# D143_01A01-V9821S.net
KiCad netlist of a schematic drawn in Altium Designer
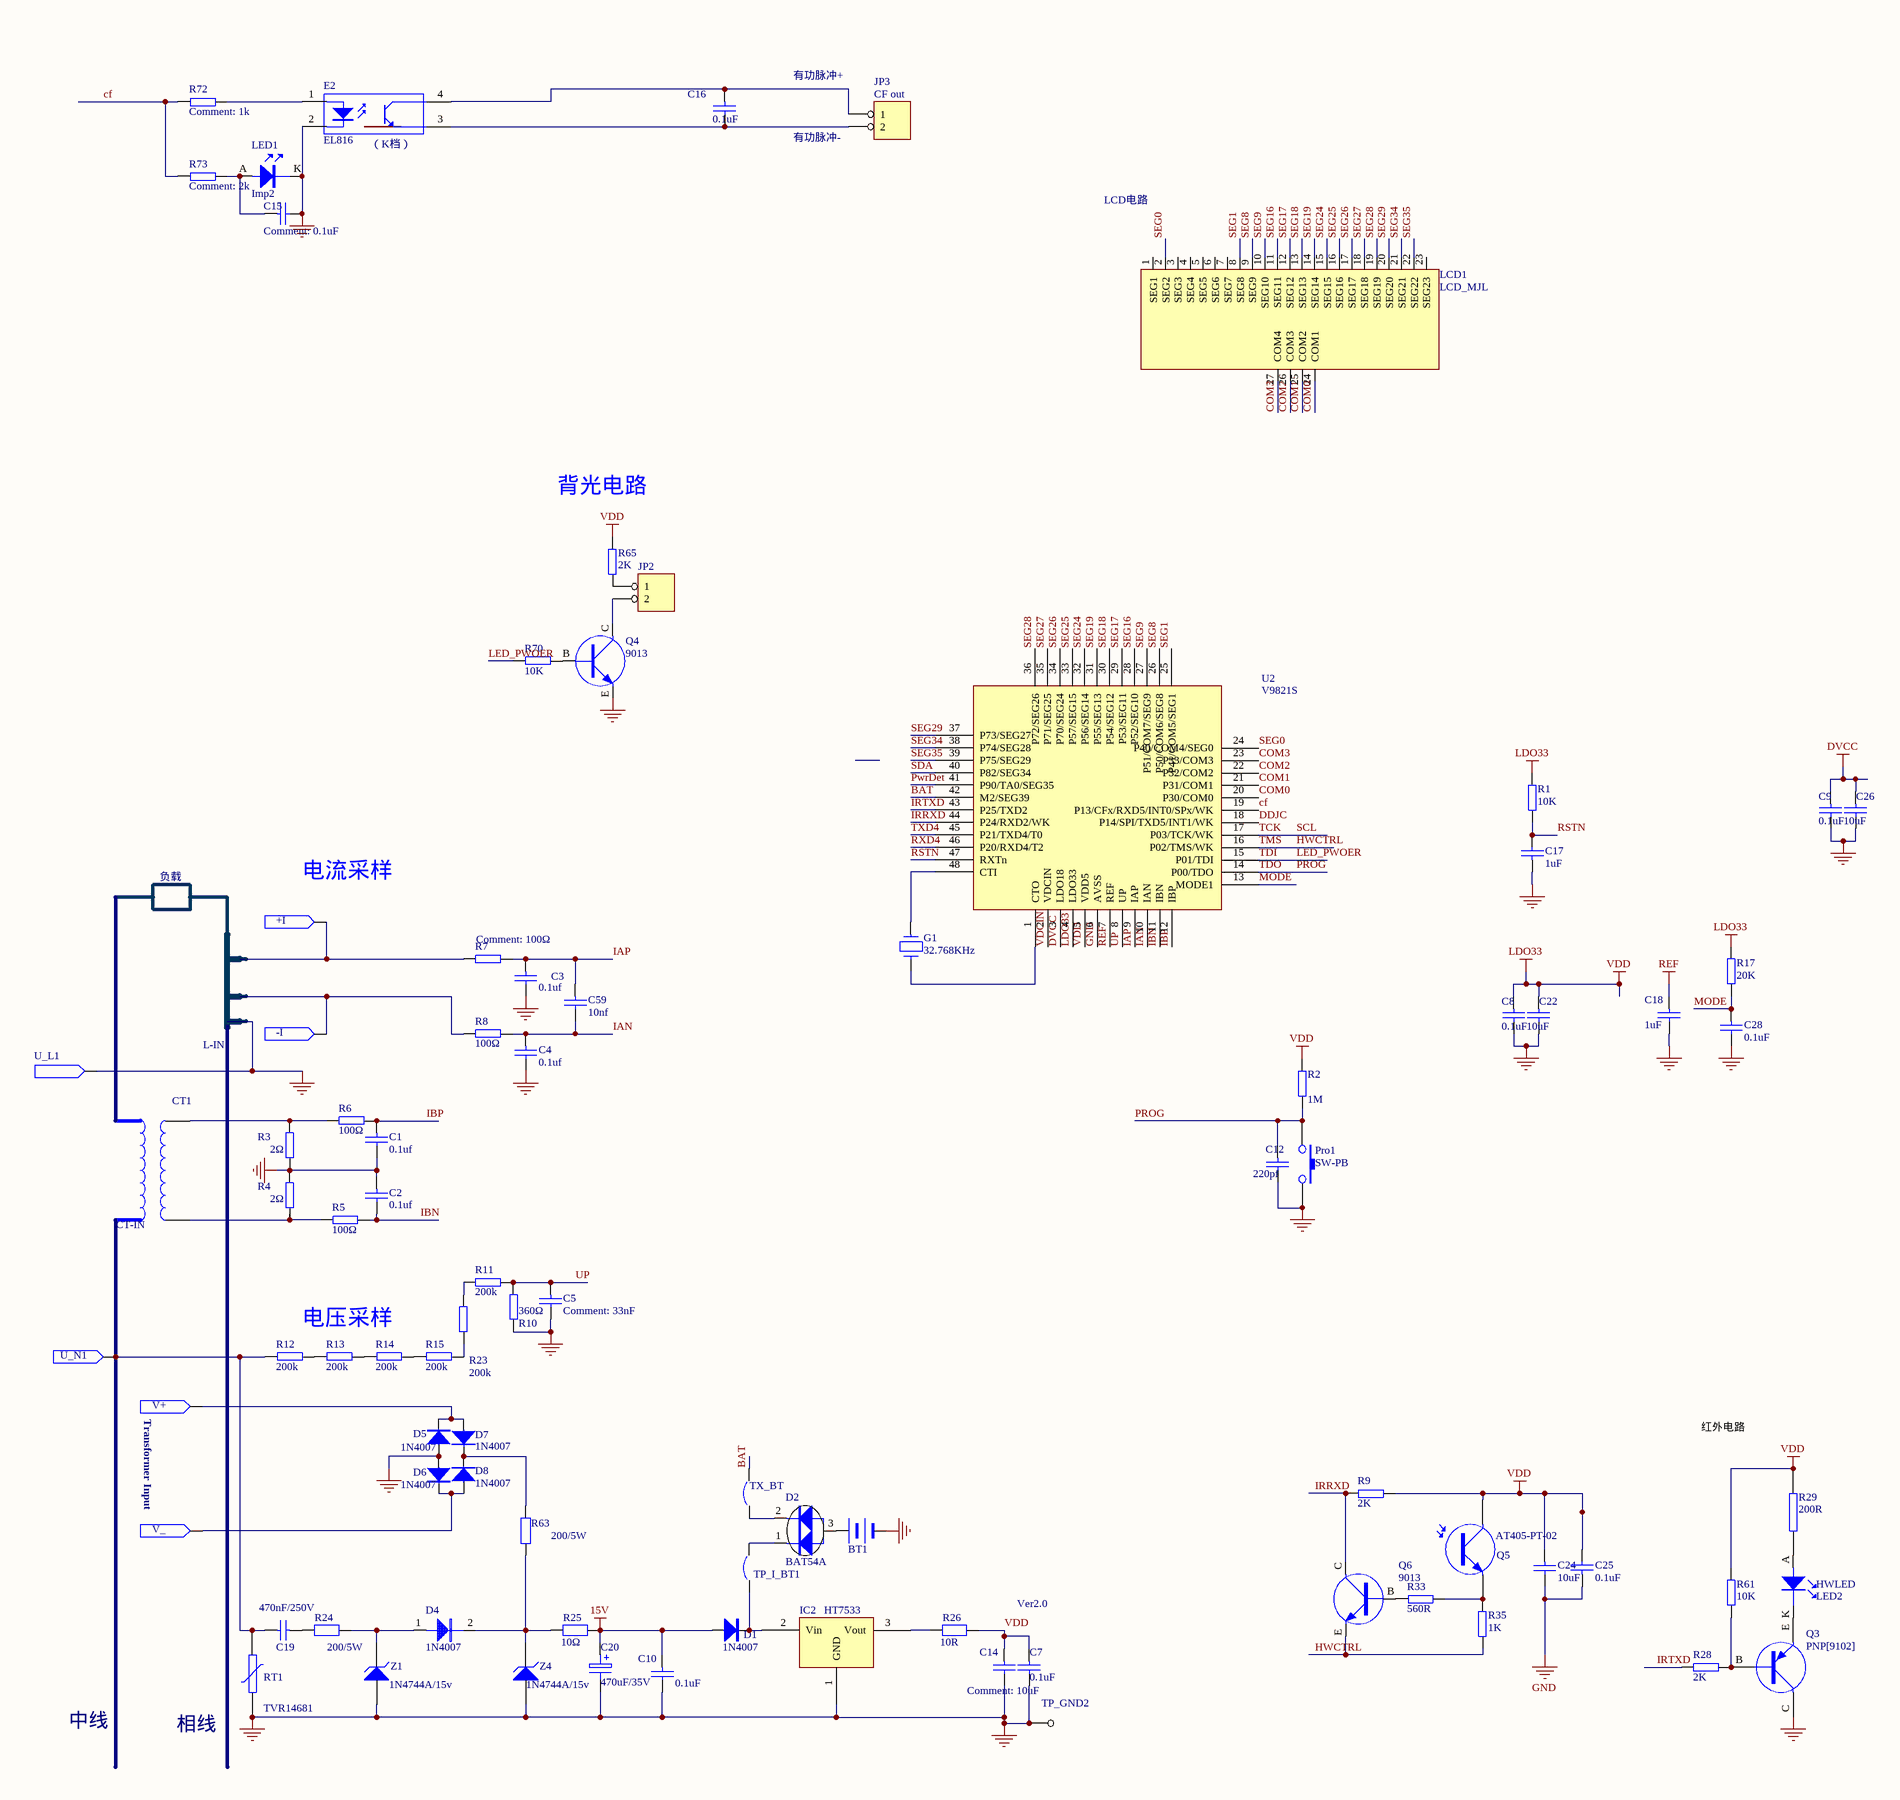
[diagram p0: D143.01A01-V9821S.SchDoc, left]
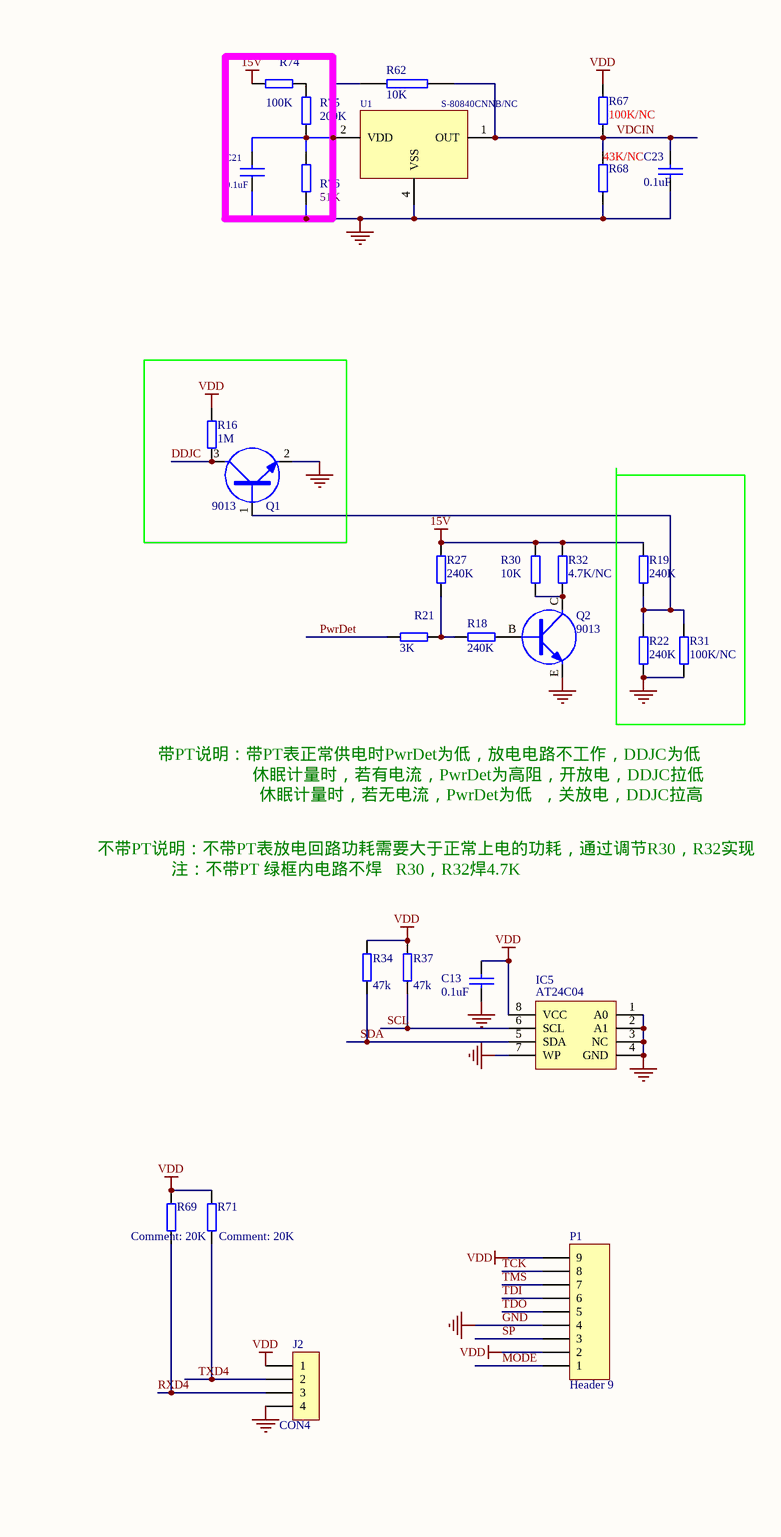
[diagram p1: D143.01A01-V9821S.SchDoc, right]

(export (version "E")
  (design (tool "Eeschema 10.0.6"))
  (components
    (comp (ref "+I") (value "~") (footprint "PAD") (libsource (lib "*") (part "Pro2C.tmp_UnNamed_44")))
    (comp (ref "-I") (value "~") (footprint "PAD") (libsource (lib "*") (part "Pro2C.tmp_UnNamed_44")))
    (comp (ref "BT1")
      (value "BT1")
      (footprint "BAT")
      (description "Battery")
      (libsource (lib "*") (part "BATTERY"))
    )
    (comp (ref "C1")
      (value "0.1uf")
      (footprint "0603C")
      (description "Capacitor")
      (libsource (lib "*") (part "CAP"))
    )
    (comp (ref "C2")
      (value "0.1uf")
      (footprint "0603C")
      (description "Capacitor")
      (libsource (lib "*") (part "CAP"))
    )
    (comp (ref "C3")
      (value "0.1uf")
      (footprint "0603C")
      (description "Capacitor")
      (libsource (lib "*") (part "CAP"))
    )
    (comp (ref "C4")
      (value "0.1uf")
      (footprint "0603C")
      (description "Capacitor")
      (libsource (lib "*") (part "CAP"))
    )
    (comp (ref "C5")
      (value "33nF")
      (footprint "0603C")
      (description "Capacitor")
      (libsource (lib "*") (part "CAP"))
    )
    (comp (ref "C7")
      (value "0.1uF")
      (footprint "0603C")
      (description "Capacitor")
      (libsource (lib "*") (part "CAP"))
    )
    (comp (ref "C8")
      (value "0.1uF")
      (footprint "0603C")
      (description "Capacitor")
      (libsource (lib "*") (part "CAP"))
    )
    (comp (ref "C9")
      (value "0.1uF")
      (footprint "0603C")
      (description "Capacitor")
      (libsource (lib "*") (part "CAP"))
    )
    (comp (ref "C10")
      (value "0.1uF")
      (footprint "0603C")
      (description "Capacitor")
      (libsource (lib "*") (part "CAP"))
    )
    (comp (ref "C12")
      (value "220pf")
      (footprint "0603C")
      (description "Capacitor")
      (libsource (lib "*") (part "CAP"))
    )
    (comp (ref "C13")
      (value "0.1uF")
      (footprint "0603C")
      (description "Capacitor")
      (libsource (lib "*") (part "CAP"))
    )
    (comp (ref "C14")
      (value "10uF")
      (footprint "0805C")
      (description "Capacitor")
      (libsource (lib "*") (part "CAP"))
    )
    (comp (ref "C15")
      (value "0.1uF")
      (footprint "0603C")
      (description "Capacitor")
      (libsource (lib "*") (part "CAP"))
    )
    (comp (ref "C16")
      (value "0.1uF")
      (footprint "0603C")
      (description "Capacitor")
      (libsource (lib "*") (part "CAP"))
    )
    (comp (ref "C17")
      (value "1uF")
      (footprint "0603C")
      (description "Capacitor")
      (libsource (lib "*") (part "CAP"))
    )
    (comp (ref "C18")
      (value "1uF")
      (footprint "0805C")
      (description "Capacitor")
      (libsource (lib "*") (part "CAP"))
    )
    (comp (ref "C19")
      (value "470nF/250V")
      (footprint "CAP0.47UF/250V")
      (description "Capacitor (Semiconductor SIM Model)")
      (fields (field (name "PUBLISHER") "*"))
      (libsource (lib "*") (part "Cap Semi"))
    )
    (comp (ref "C20")
      (value "470uF/35V")
      (footprint "RB.2/.4")
      (libsource (lib "*") (part "ProB204.TMP_UnNamed_47"))
    )
    (comp (ref "C21") (value "0.1uF") (footprint "0603C") (libsource (lib "*") (part "CAP NP")))
    (comp (ref "C22")
      (value "10uF")
      (footprint "0805C")
      (description "Capacitor")
      (libsource (lib "*") (part "CAP"))
    )
    (comp (ref "C23")
      (value "0.1uF")
      (footprint "0603C")
      (description "Capacitor")
      (libsource (lib "*") (part "CAP"))
    )
    (comp (ref "C24")
      (value "10uF")
      (footprint "0805c")
      (description "Capacitor")
      (libsource (lib "*") (part "CAP"))
    )
    (comp (ref "C25") (value "0.1uF") (footprint "0603C") (libsource (lib "*") (part "CAP")))
    (comp (ref "C26")
      (value "10uF")
      (footprint "0805C")
      (description "Capacitor")
      (libsource (lib "*") (part "CAP"))
    )
    (comp (ref "C28")
      (value "0.1uF")
      (footprint "0603C")
      (description "Capacitor")
      (libsource (lib "*") (part "CAP"))
    )
    (comp (ref "C59")
      (value "10nf")
      (footprint "0603C")
      (description "Capacitor")
      (libsource (lib "*") (part "CAP"))
    )
    (comp (ref "CT1") (value "CT-IN") (footprint "CT") (libsource (lib "*") (part "WZ-CT-S")))
    (comp (ref "D1") (value "1N4007") (footprint "MLL41") (libsource (lib "*") (part "WF_D")))
    (comp (ref "D2")
      (value "BAT54A")
      (footprint "SOT_23")
      (description "共阳")
      (libsource (lib "BASIC") (part "BAT54A"))
    )
    (comp (ref "D4")
      (value "1N4007")
      (footprint "DIODE-L")
      (libsource (lib "*") (part "ProB204.TMP_UnNamed_35"))
    )
    (comp (ref "D5") (value "1N4007") (footprint "MLL41") (libsource (lib "*") (part "WF_D")))
    (comp (ref "D6") (value "1N4007") (footprint "MLL41") (libsource (lib "*") (part "WF_D")))
    (comp (ref "D7") (value "1N4007") (footprint "MLL41") (libsource (lib "*") (part "WF_D")))
    (comp (ref "D8") (value "1N4007") (footprint "MLL41") (libsource (lib "*") (part "WF_D")))
    (comp (ref "E2") (value "EL816") (footprint "SOP-4") (libsource (lib "*") (part "TL521")))
    (comp (ref "G1")
      (value "32.768KHz")
      (footprint "OSC")
      (description "Crystal")
      (libsource (lib "*") (part "WF_X_1"))
    )
    (comp (ref "IC2") (value "HT7533") (footprint "SOT-89") (libsource (lib "*") (part "HT7150")))
    (comp (ref "IC5") (value "AT24C04") (footprint "SOP8") (libsource (lib "*") (part "AT24256")))
    (comp (ref "J2")
      (value "CON4")
      (footprint "SIP4")
      (description "Connector")
      (libsource (lib "*") (part "CON4"))
    )
    (comp (ref "JP2") (value "~") (footprint "SIP2") (libsource (lib "*") (part "HEADER 2")))
    (comp (ref "JP3") (value "CF out") (footprint "ct") (libsource (lib "*") (part "HEADER 2")))
    (comp (ref "LCD1") (value "LCD_MJL") (footprint "LCD_MJL") (libsource (lib "*") (part "LCD_MJL")))
    (comp (ref "LED1") (value "Imp2") (footprint "LED") (libsource (lib "*") (part "LED")))
    (comp (ref "LED2") (value "HWLED") (footprint "LED") (libsource (lib "*") (part "LED")))
    (comp (ref "P1")
      (value "Header 9")
      (footprint "CONNECT1")
      (description "Header, 9-Pin")
      (fields (field (name "PUBLISHER") "Altium Limited"))
      (libsource (lib "*") (part "Header 9"))
    )
    (comp (ref "Pro1") (value "SW-PB") (footprint "KEY1") (libsource (lib "*") (part "SW-PB")))
    (comp (ref "Q1") (value "9013") (footprint "SOT-23") (libsource (lib "") (part "NPN_1")))
    (comp (ref "Q2") (value "9013") (footprint "SOT-23-EBC") (libsource (lib "*") (part "NPN")))
    (comp (ref "Q3") (value "PNP[9102]") (footprint "SOT-23-EBC") (libsource (lib "*") (part "PNP[9102]")))
    (comp (ref "Q4") (value "9013") (footprint "SOT-23-EBC") (libsource (lib "*") (part "NPN")))
    (comp (ref "Q5") (value "AT405-PT-02") (footprint "LED2") (libsource (lib "*") (part "3244SC")))
    (comp (ref "Q6") (value "9013") (footprint "SOT-23-EBC") (libsource (lib "*") (part "NPN")))
    (comp (ref "R1") (value "10K") (footprint "0603R") (libsource (lib "*") (part "REST_S")))
    (comp (ref "R2") (value "1M") (footprint "0603R") (libsource (lib "*") (part "REST_S")))
    (comp (ref "R3") (value "2Ω") (footprint "0805R") (libsource (lib "*") (part "REST_S")))
    (comp (ref "R4") (value "2Ω") (footprint "0805R") (libsource (lib "*") (part "REST_S")))
    (comp (ref "R5") (value "100Ω") (footprint "0603R") (libsource (lib "*") (part "REST_S")))
    (comp (ref "R6") (value "100Ω") (footprint "0603R") (libsource (lib "*") (part "REST_S")))
    (comp (ref "R7") (value "100Ω") (footprint "0603R") (libsource (lib "*") (part "REST_S")))
    (comp (ref "R8") (value "100Ω") (footprint "0603R") (libsource (lib "*") (part "REST_S")))
    (comp (ref "R9") (value "2K") (footprint "0603R") (libsource (lib "*") (part "R")))
    (comp (ref "R10") (value "360Ω") (footprint "0805R") (libsource (lib "*") (part "REST_S")))
    (comp (ref "R11") (value "200k") (footprint "0805R") (libsource (lib "*") (part "REST_S")))
    (comp (ref "R12") (value "200k") (footprint "0805R") (libsource (lib "*") (part "REST_S")))
    (comp (ref "R13") (value "200k") (footprint "0805R") (libsource (lib "*") (part "REST_S")))
    (comp (ref "R14") (value "200k") (footprint "0805R") (libsource (lib "*") (part "REST_S")))
    (comp (ref "R15") (value "200k") (footprint "0805R") (libsource (lib "*") (part "REST_S")))
    (comp (ref "R16") (value "1M") (footprint "0603R") (libsource (lib "*") (part "REST_S")))
    (comp (ref "R17") (value "20K") (footprint "0603R") (libsource (lib "*") (part "REST_S")))
    (comp (ref "R18") (value "240K") (footprint "0603R") (libsource (lib "*") (part "REST_S")))
    (comp (ref "R19") (value "240K") (footprint "0603R") (libsource (lib "*") (part "REST_S")))
    (comp (ref "R21") (value "3K") (footprint "0603R") (libsource (lib "*") (part "REST_S")))
    (comp (ref "R22") (value "240K") (footprint "0603R") (libsource (lib "*") (part "REST_S")))
    (comp (ref "R23") (value "200k") (footprint "0805R") (libsource (lib "*") (part "REST_S")))
    (comp (ref "R24")
      (value "200/5W")
      (footprint "AXIAL0.8A")
      (description "Resistor")
      (fields (field (name "PUBLISHER") "*"))
      (libsource (lib "*") (part "Res2"))
    )
    (comp (ref "R25")
      (value "10Ω")
      (footprint "0805R")
      (description "Resistor")
      (fields (field (name "PUBLISHER") "*"))
      (libsource (lib "*") (part "Res2"))
    )
    (comp (ref "R26")
      (value "10R")
      (footprint "0805R")
      (description "Resistor")
      (fields (field (name "PUBLISHER") "*"))
      (libsource (lib "*") (part "Res2"))
    )
    (comp (ref "R27") (value "240K") (footprint "0603R") (libsource (lib "*") (part "REST_S")))
    (comp (ref "R28") (value "2K") (footprint "0603R") (libsource (lib "*") (part "R")))
    (comp (ref "R29") (value "200R") (footprint "0603R") (libsource (lib "*") (part "RES2")))
    (comp (ref "R30") (value "10K") (footprint "0603R") (libsource (lib "*") (part "REST_S")))
    (comp (ref "R31") (value "100K/NC") (footprint "0603R") (libsource (lib "*") (part "REST_S")))
    (comp (ref "R32") (value "4.7K/NC") (footprint "0603R") (libsource (lib "*") (part "REST_S")))
    (comp (ref "R33") (value "560R") (footprint "0603R") (libsource (lib "*") (part "R")))
    (comp (ref "R34") (value "47k") (footprint "0603R") (libsource (lib "*") (part "REST_S")))
    (comp (ref "R35") (value "1K") (footprint "0603R") (libsource (lib "*") (part "R")))
    (comp (ref "R37") (value "47k") (footprint "0603R") (libsource (lib "*") (part "REST_S")))
    (comp (ref "R61") (value "10K") (footprint "0603R") (libsource (lib "*") (part "R")))
    (comp (ref "R62") (value "10K") (footprint "0603R") (libsource (lib "*") (part "RES2")))
    (comp (ref "R63")
      (value "200/5W")
      (footprint "AXIAL0.8A")
      (description "Resistor")
      (fields (field (name "PUBLISHER") "*"))
      (libsource (lib "") (part "Res2_1"))
    )
    (comp (ref "R65") (value "2K") (footprint "0603R") (libsource (lib "*") (part "R")))
    (comp (ref "R67") (value "100K/NC") (footprint "0603R") (libsource (lib "*") (part "REST_S")))
    (comp (ref "R68") (value "43K/NC") (footprint "0603R") (libsource (lib "*") (part "REST_S")))
    (comp (ref "R69") (value "20K") (footprint "0603R") (libsource (lib "*") (part "REST_S")))
    (comp (ref "R70") (value "10K") (footprint "0603R") (libsource (lib "*") (part "R")))
    (comp (ref "R71") (value "20K") (footprint "0603R") (libsource (lib "*") (part "REST_S")))
    (comp (ref "R72") (value "1k") (footprint "0603R") (libsource (lib "*") (part "REST_S")))
    (comp (ref "R73") (value "2k") (footprint "0603R") (libsource (lib "*") (part "REST_S")))
    (comp (ref "R74") (value "100K") (footprint "0805R") (libsource (lib "*") (part "REST_S")))
    (comp (ref "R75") (value "200K") (footprint "0805R") (libsource (lib "*") (part "REST_S")))
    (comp (ref "R76") (value "51K") (footprint "0805R") (libsource (lib "*") (part "REST_S")))
    (comp (ref "RT1") (value "TVR14681") (footprint "YM20K681") (libsource (lib "*") (part "WF_RESV")))
    (comp (ref "TP_GND2")
      (value "TP")
      (footprint "TEST0")
      (description "TEST POINT")
      (libsource (lib "*") (part "TP_T"))
    )
    (comp (ref "TP_I_BT1")
      (value "CIRCUIT BREAKER")
      (footprint "JUMP")
      (description "Circuit Breaker")
      (libsource (lib "*") (part "CIRCUIT BREAKER"))
    )
    (comp (ref "TX_BT")
      (value "CIRCUIT BREAKER")
      (footprint "JUMP")
      (description "Circuit Breaker")
      (libsource (lib "*") (part "CIRCUIT BREAKER"))
    )
    (comp (ref "U1")
      (value "S-80840CNNB/NC")
      (footprint "SC-82AB")
      (description "电源检测IC")
      (libsource (lib "*") (part "S808XX_CLNB"))
    )
    (comp (ref "U2") (value "V9821S") (libsource (lib "Schlib1") (part "Component_1")))
    (comp (ref "U_L1") (value "~") (footprint "PAD") (libsource (lib "*") (part "Pro2C.tmp_UnNamed_44")))
    (comp (ref "U_N1") (value "~") (footprint "PAD") (libsource (lib "*") (part "Pro2C.tmp_UnNamed_44")))
    (comp (ref "V+") (value "~") (footprint "PAD") (libsource (lib "*") (part "Pro2C.tmp_UnNamed_44")))
    (comp (ref "V_") (value "~") (footprint "PAD") (libsource (lib "*") (part "Pro2C.tmp_UnNamed_44")))
    (comp (ref "Z1")
      (value "1N4744A/15v")
      (footprint "DIODE")
      (description "One Watt Zener")
      (libsource (lib "*") (part "1N4734A"))
    )
    (comp (ref "Z4")
      (value "1N4744A/15v")
      (footprint "DIODE")
      (description "One Watt Zener")
      (libsource (lib "*") (part "1N4734A"))
    )
  )
  (nets
    (net (code "1") (name "/BAT") (class "Default")
      (node (ref "TX_BT") (pin "2") (pinfunction "2_2") (pintype "passive"))
      (node (ref "U2") (pin "42") (pinfunction "M2/SEG39_42") (pintype "passive"))
    )
    (net (code "2") (name "/COM0") (class "Default")
      (node (ref "LCD1") (pin "24") (pinfunction "COM1_24") (pintype "passive"))
      (node (ref "U2") (pin "20") (pinfunction "P30/COM0_20") (pintype "passive"))
    )
    (net (code "3") (name "/COM1") (class "Default")
      (node (ref "LCD1") (pin "25") (pinfunction "COM2_25") (pintype "passive"))
      (node (ref "U2") (pin "21") (pinfunction "P31/COM1_21") (pintype "passive"))
    )
    (net (code "4") (name "/COM2") (class "Default")
      (node (ref "LCD1") (pin "26") (pinfunction "COM3_26") (pintype "passive"))
      (node (ref "U2") (pin "22") (pinfunction "P32/COM2_22") (pintype "passive"))
    )
    (net (code "5") (name "/COM3") (class "Default")
      (node (ref "LCD1") (pin "27") (pinfunction "COM4_27") (pintype "passive"))
      (node (ref "U2") (pin "23") (pinfunction "P33/COM3_23") (pintype "passive"))
    )
    (net (code "6") (name "/DDJC") (class "Default")
      (node (ref "Q1") (pin "3") (pinfunction "C_3") (pintype "passive"))
      (node (ref "R16") (pin "1") (pinfunction "1_1") (pintype "passive"))
      (node (ref "U2") (pin "18") (pinfunction "P14/SPI/TXD5/INT1/WK_18") (pintype "passive"))
    )
    (net (code "7") (name "/HWCTRL") (class "Default")
      (node (ref "P1") (pin "7") (pinfunction "7_7") (pintype "passive"))
      (node (ref "Q6") (pin "E") (pinfunction "E_E") (pintype "passive"))
      (node (ref "R35") (pin "1") (pintype "passive"))
      (node (ref "U2") (pin "16") (pinfunction "P02/TMS/WK_16") (pintype "passive"))
    )
    (net (code "8") (name "/IAN") (class "Default")
      (node (ref "C4") (pin "1") (pinfunction "1_1") (pintype "passive"))
      (node (ref "C59") (pin "2") (pinfunction "2_2") (pintype "passive"))
      (node (ref "R8") (pin "1") (pinfunction "1_1") (pintype "passive"))
      (node (ref "U2") (pin "10") (pinfunction "IAN_10") (pintype "passive"))
    )
    (net (code "9") (name "/IAP") (class "Default")
      (node (ref "C3") (pin "1") (pinfunction "1_1") (pintype "passive"))
      (node (ref "C59") (pin "1") (pinfunction "1_1") (pintype "passive"))
      (node (ref "R7") (pin "1") (pinfunction "1_1") (pintype "passive"))
      (node (ref "U2") (pin "9") (pinfunction "IAP_9") (pintype "passive"))
    )
    (net (code "10") (name "/IBN") (class "Default")
      (node (ref "C2") (pin "2") (pinfunction "2_2") (pintype "passive"))
      (node (ref "R5") (pin "1") (pinfunction "1_1") (pintype "passive"))
      (node (ref "U2") (pin "11") (pinfunction "IBN_11") (pintype "passive"))
    )
    (net (code "11") (name "/IBP") (class "Default")
      (node (ref "C1") (pin "1") (pinfunction "1_1") (pintype "passive"))
      (node (ref "R6") (pin "1") (pinfunction "1_1") (pintype "passive"))
      (node (ref "U2") (pin "12") (pinfunction "IBP_12") (pintype "passive"))
    )
    (net (code "12") (name "/IRRXD") (class "Default")
      (node (ref "Q6") (pin "C") (pinfunction "C_C") (pintype "passive"))
      (node (ref "R9") (pin "1") (pintype "passive"))
      (node (ref "U2") (pin "44") (pinfunction "P24/RXD2/WK_44") (pintype "passive"))
    )
    (net (code "13") (name "/IRTXD") (class "Default")
      (node (ref "R28") (pin "2") (pintype "passive"))
      (node (ref "U2") (pin "43") (pinfunction "P25/TXD2_43") (pintype "passive"))
    )
    (net (code "14") (name "/LED_PWOER") (class "Default")
      (node (ref "P1") (pin "6") (pinfunction "6_6") (pintype "passive"))
      (node (ref "R70") (pin "2") (pintype "passive"))
      (node (ref "U2") (pin "15") (pinfunction "P01/TDI_15") (pintype "passive"))
    )
    (net (code "15") (name "/MODE") (class "Default")
      (node (ref "C28") (pin "1") (pinfunction "1_1") (pintype "passive"))
      (node (ref "P1") (pin "1") (pinfunction "1_1") (pintype "passive"))
      (node (ref "R17") (pin "2") (pinfunction "2_2") (pintype "passive"))
      (node (ref "U2") (pin "13") (pinfunction "MODE1_13") (pintype "passive"))
    )
    (net (code "16") (name "/PROG") (class "Default")
      (node (ref "C12") (pin "1") (pinfunction "1_1") (pintype "passive"))
      (node (ref "P1") (pin "5") (pinfunction "5_5") (pintype "passive"))
      (node (ref "Pro1") (pin "1") (pinfunction "1_1") (pintype "passive"))
      (node (ref "Pro1") (pin "3") (pinfunction "3_3") (pintype "passive"))
      (node (ref "R2") (pin "1") (pinfunction "1_1") (pintype "passive"))
      (node (ref "U2") (pin "14") (pinfunction "P00/TDO_14") (pintype "passive"))
    )
    (net (code "17") (name "/PwrDet") (class "Default")
      (node (ref "R21") (pin "1") (pinfunction "1_1") (pintype "passive"))
      (node (ref "U2") (pin "41") (pinfunction "P90/TA0/SEG35_41") (pintype "passive"))
    )
    (net (code "18") (name "/RSTN") (class "Default")
      (node (ref "C17") (pin "2") (pinfunction "2_2") (pintype "passive"))
      (node (ref "R1") (pin "1") (pinfunction "1_1") (pintype "passive"))
      (node (ref "U2") (pin "47") (pinfunction "RXTn_47") (pintype "passive"))
    )
    (net (code "19") (name "/RXD4") (class "Default")
      (node (ref "J2") (pin "3") (pinfunction "3_3") (pintype "passive"))
      (node (ref "R69") (pin "2") (pinfunction "2_2") (pintype "passive"))
      (node (ref "U2") (pin "46") (pinfunction "P20/RXD4/T2_46") (pintype "passive"))
    )
    (net (code "20") (name "/SCL") (class "Default")
      (node (ref "IC5") (pin "6") (pinfunction "SCL_6") (pintype "passive"))
      (node (ref "P1") (pin "8") (pinfunction "8_8") (pintype "passive"))
      (node (ref "R37") (pin "1") (pinfunction "1_1") (pintype "passive"))
      (node (ref "U2") (pin "17") (pinfunction "P03/TCK/WK_17") (pintype "passive"))
    )
    (net (code "21") (name "/SDA") (class "Default")
      (node (ref "IC5") (pin "5") (pinfunction "SDA_5") (pintype "passive"))
      (node (ref "R34") (pin "1") (pinfunction "1_1") (pintype "passive"))
      (node (ref "U2") (pin "40") (pinfunction "P82/SEG34_40") (pintype "passive"))
    )
    (net (code "22") (name "/SEG0") (class "Default")
      (node (ref "LCD1") (pin "2") (pinfunction "SEG2_2") (pintype "passive"))
      (node (ref "U2") (pin "24") (pinfunction "P40/COM4/SEG0_24") (pintype "passive"))
    )
    (net (code "23") (name "/SEG1") (class "Default")
      (node (ref "LCD1") (pin "8") (pinfunction "SEG8_8") (pintype "passive"))
      (node (ref "U2") (pin "25") (pinfunction "P41/COM5/SEG1_25") (pintype "passive"))
    )
    (net (code "24") (name "/SEG8") (class "Default")
      (node (ref "LCD1") (pin "9") (pinfunction "SEG9_9") (pintype "passive"))
      (node (ref "U2") (pin "26") (pinfunction "P50/COM6/SEG8_26") (pintype "passive"))
    )
    (net (code "25") (name "/SEG9") (class "Default")
      (node (ref "LCD1") (pin "10") (pinfunction "SEG10_10") (pintype "passive"))
      (node (ref "U2") (pin "27") (pinfunction "P51/COM7/SEG9_27") (pintype "passive"))
    )
    (net (code "26") (name "/SEG16") (class "Default")
      (node (ref "LCD1") (pin "11") (pinfunction "SEG11_11") (pintype "passive"))
      (node (ref "U2") (pin "28") (pinfunction "P52/SEG10_28") (pintype "passive"))
    )
    (net (code "27") (name "/SEG17") (class "Default")
      (node (ref "LCD1") (pin "12") (pinfunction "SEG12_12") (pintype "passive"))
      (node (ref "U2") (pin "29") (pinfunction "P53/SEG11_29") (pintype "passive"))
    )
    (net (code "28") (name "/SEG18") (class "Default")
      (node (ref "LCD1") (pin "13") (pinfunction "SEG13_13") (pintype "passive"))
      (node (ref "U2") (pin "30") (pinfunction "P54/SEG12_30") (pintype "passive"))
    )
    (net (code "29") (name "/SEG19") (class "Default")
      (node (ref "LCD1") (pin "14") (pinfunction "SEG14_14") (pintype "passive"))
      (node (ref "U2") (pin "31") (pinfunction "P55/SEG13_31") (pintype "passive"))
    )
    (net (code "30") (name "/SEG24") (class "Default")
      (node (ref "LCD1") (pin "15") (pinfunction "SEG15_15") (pintype "passive"))
      (node (ref "U2") (pin "32") (pinfunction "P56/SEG14_32") (pintype "passive"))
    )
    (net (code "31") (name "/SEG25") (class "Default")
      (node (ref "LCD1") (pin "16") (pinfunction "SEG16_16") (pintype "passive"))
      (node (ref "U2") (pin "33") (pinfunction "P57/SEG15_33") (pintype "passive"))
    )
    (net (code "32") (name "/SEG26") (class "Default")
      (node (ref "LCD1") (pin "17") (pinfunction "SEG17_17") (pintype "passive"))
      (node (ref "U2") (pin "34") (pinfunction "P70/SEG24_34") (pintype "passive"))
    )
    (net (code "33") (name "/SEG27") (class "Default")
      (node (ref "LCD1") (pin "18") (pinfunction "SEG18_18") (pintype "passive"))
      (node (ref "U2") (pin "35") (pinfunction "P71/SEG25_35") (pintype "passive"))
    )
    (net (code "34") (name "/SEG28") (class "Default")
      (node (ref "LCD1") (pin "19") (pinfunction "SEG19_19") (pintype "passive"))
      (node (ref "U2") (pin "36") (pinfunction "P72/SEG26_36") (pintype "passive"))
    )
    (net (code "35") (name "/SEG29") (class "Default")
      (node (ref "LCD1") (pin "20") (pinfunction "SEG20_20") (pintype "passive"))
      (node (ref "U2") (pin "37") (pinfunction "P73/SEG27_37") (pintype "passive"))
    )
    (net (code "36") (name "/SEG34") (class "Default")
      (node (ref "LCD1") (pin "21") (pinfunction "SEG21_21") (pintype "passive"))
      (node (ref "U2") (pin "38") (pinfunction "P74/SEG28_38") (pintype "passive"))
    )
    (net (code "37") (name "/SEG35") (class "Default")
      (node (ref "LCD1") (pin "22") (pinfunction "SEG22_22") (pintype "passive"))
      (node (ref "U2") (pin "39") (pinfunction "P75/SEG29_39") (pintype "passive"))
    )
    (net (code "38") (name "/SP") (class "Default")
      (node (ref "P1") (pin "3") (pinfunction "3_3") (pintype "passive"))
    )
    (net (code "39") (name "/TXD4") (class "Default")
      (node (ref "J2") (pin "2") (pinfunction "2_2") (pintype "passive"))
      (node (ref "R71") (pin "2") (pinfunction "2_2") (pintype "passive"))
      (node (ref "U2") (pin "45") (pinfunction "P21/TXD4/T0_45") (pintype "passive"))
    )
    (net (code "40") (name "/UP") (class "Default")
      (node (ref "C5") (pin "1") (pinfunction "1_1") (pintype "passive"))
      (node (ref "R10") (pin "1") (pinfunction "1_1") (pintype "passive"))
      (node (ref "R11") (pin "2") (pinfunction "2_2") (pintype "passive"))
      (node (ref "U2") (pin "8") (pinfunction "UP_8") (pintype "passive"))
    )
    (net (code "41") (name "/VDCIN") (class "Default")
      (node (ref "C23") (pin "1") (pinfunction "1_1") (pintype "passive"))
      (node (ref "R62") (pin "1") (pinfunction "1_1") (pintype "passive"))
      (node (ref "R67") (pin "1") (pinfunction "1_1") (pintype "passive"))
      (node (ref "R68") (pin "2") (pinfunction "2_2") (pintype "passive"))
      (node (ref "U1") (pin "1") (pinfunction "OUT_1") (pintype "passive"))
      (node (ref "U2") (pin "2") (pinfunction "VDCIN_2") (pintype "passive"))
    )
    (net (code "42") (name "/cf") (class "Default")
      (node (ref "R72") (pin "1") (pinfunction "1_1") (pintype "passive"))
      (node (ref "R73") (pin "1") (pinfunction "1_1") (pintype "passive"))
      (node (ref "U2") (pin "19") (pinfunction "P13/CFx/RXD5/INT0/SPx/WK_19") (pintype "passive"))
    )
    (net (code "43") (name "15V") (class "Default")
      (node (ref "C10") (pin "1") (pinfunction "1_1") (pintype "passive"))
      (node (ref "C20") (pin "1") (pintype "passive"))
      (node (ref "D1") (pin "1") (pinfunction "A_1") (pintype "passive"))
      (node (ref "R19") (pin "1") (pinfunction "1_1") (pintype "passive"))
      (node (ref "R25") (pin "1") (pinfunction "1_1") (pintype "passive"))
      (node (ref "R27") (pin "1") (pinfunction "1_1") (pintype "passive"))
      (node (ref "R30") (pin "2") (pinfunction "2_2") (pintype "passive"))
      (node (ref "R32") (pin "2") (pinfunction "2_2") (pintype "passive"))
      (node (ref "R74") (pin "2") (pinfunction "2_2") (pintype "passive"))
    )
    (net (code "44") (name "DVCC") (class "Default")
      (node (ref "C26") (pin "1") (pinfunction "1_1") (pintype "passive"))
      (node (ref "C9") (pin "1") (pinfunction "1_1") (pintype "passive"))
      (node (ref "U2") (pin "3") (pinfunction "LDO18_3") (pintype "passive"))
    )
    (net (code "45") (name "GND") (class "Default")
      (node (ref "BT1") (pin "2") (pinfunction "-_2") (pintype "passive"))
      (node (ref "C1") (pin "2") (pinfunction "2_2") (pintype "passive"))
      (node (ref "C10") (pin "2") (pinfunction "2_2") (pintype "passive"))
      (node (ref "C12") (pin "2") (pinfunction "2_2") (pintype "passive"))
      (node (ref "C13") (pin "2") (pinfunction "2_2") (pintype "passive"))
      (node (ref "C14") (pin "2") (pinfunction "2_2") (pintype "passive"))
      (node (ref "C15") (pin "2") (pinfunction "2_2") (pintype "passive"))
      (node (ref "C17") (pin "1") (pinfunction "1_1") (pintype "passive"))
      (node (ref "C18") (pin "2") (pinfunction "2_2") (pintype "passive"))
      (node (ref "C2") (pin "1") (pinfunction "1_1") (pintype "passive"))
      (node (ref "C20") (pin "2") (pintype "passive"))
      (node (ref "C21") (pin "1") (pinfunction "1_1") (pintype "passive"))
      (node (ref "C22") (pin "2") (pinfunction "2_2") (pintype "passive"))
      (node (ref "C23") (pin "2") (pinfunction "2_2") (pintype "passive"))
      (node (ref "C24") (pin "2") (pinfunction "2_2") (pintype "passive"))
      (node (ref "C25") (pin "1") (pinfunction "1_1") (pintype "passive"))
      (node (ref "C26") (pin "2") (pinfunction "2_2") (pintype "passive"))
      (node (ref "C28") (pin "2") (pinfunction "2_2") (pintype "passive"))
      (node (ref "C3") (pin "2") (pinfunction "2_2") (pintype "passive"))
      (node (ref "C4") (pin "2") (pinfunction "2_2") (pintype "passive"))
      (node (ref "C5") (pin "2") (pinfunction "2_2") (pintype "passive"))
      (node (ref "C7") (pin "2") (pinfunction "2_2") (pintype "passive"))
      (node (ref "C8") (pin "2") (pinfunction "2_2") (pintype "passive"))
      (node (ref "C9") (pin "2") (pinfunction "2_2") (pintype "passive"))
      (node (ref "D5") (pin "1") (pinfunction "A_1") (pintype "passive"))
      (node (ref "D6") (pin "1") (pinfunction "A_1") (pintype "passive"))
      (node (ref "E2") (pin "2") (pinfunction "2_2") (pintype "passive"))
      (node (ref "IC2") (pin "1") (pinfunction "GND_1") (pintype "passive"))
      (node (ref "IC5") (pin "1") (pinfunction "A0_1") (pintype "passive"))
      (node (ref "IC5") (pin "2") (pinfunction "A1_2") (pintype "passive"))
      (node (ref "IC5") (pin "3") (pinfunction "NC_3") (pintype "passive"))
      (node (ref "IC5") (pin "4") (pinfunction "GND_4") (pintype "passive"))
      (node (ref "IC5") (pin "7") (pinfunction "WP_7") (pintype "passive"))
      (node (ref "J2") (pin "4") (pinfunction "4_4") (pintype "passive"))
      (node (ref "LED1") (pin "K") (pinfunction "2_K") (pintype "passive"))
      (node (ref "P1") (pin "4") (pinfunction "4_4") (pintype "passive"))
      (node (ref "Pro1") (pin "2") (pinfunction "2_2") (pintype "passive"))
      (node (ref "Pro1") (pin "4") (pinfunction "4_4") (pintype "passive"))
      (node (ref "Q1") (pin "2") (pinfunction "E_2") (pintype "passive"))
      (node (ref "Q2") (pin "E") (pinfunction "E_E") (pintype "passive"))
      (node (ref "Q3") (pin "C") (pinfunction "C_C") (pintype "passive"))
      (node (ref "Q4") (pin "E") (pinfunction "E_E") (pintype "passive"))
      (node (ref "R10") (pin "2") (pinfunction "2_2") (pintype "passive"))
      (node (ref "R22") (pin "2") (pinfunction "2_2") (pintype "passive"))
      (node (ref "R3") (pin "2") (pinfunction "2_2") (pintype "passive"))
      (node (ref "R31") (pin "1") (pinfunction "1_1") (pintype "passive"))
      (node (ref "R4") (pin "1") (pinfunction "1_1") (pintype "passive"))
      (node (ref "R68") (pin "1") (pinfunction "1_1") (pintype "passive"))
      (node (ref "R76") (pin "1") (pinfunction "1_1") (pintype "passive"))
      (node (ref "RT1") (pin "2") (pinfunction "2_2") (pintype "passive"))
      (node (ref "TP_GND2") (pin "0") (pinfunction "0_0") (pintype "passive"))
      (node (ref "U1") (pin "4") (pinfunction "VSS_4") (pintype "passive"))
      (node (ref "U2") (pin "6") (pinfunction "AVSS_6") (pintype "passive"))
      (node (ref "U_L1") (pin "1") (pintype "passive"))
      (node (ref "Z1") (pin "1") (pinfunction "A_1") (pintype "passive"))
      (node (ref "Z4") (pin "1") (pinfunction "A_1") (pintype "passive"))
    )
    (net (code "46") (name "LDO33") (class "Default")
      (node (ref "C13") (pin "1") (pinfunction "1_1") (pintype "passive"))
      (node (ref "C14") (pin "1") (pinfunction "1_1") (pintype "passive"))
      (node (ref "C22") (pin "1") (pinfunction "1_1") (pintype "passive"))
      (node (ref "C24") (pin "1") (pinfunction "1_1") (pintype "passive"))
      (node (ref "C25") (pin "2") (pinfunction "2_2") (pintype "passive"))
      (node (ref "C7") (pin "1") (pinfunction "1_1") (pintype "passive"))
      (node (ref "C8") (pin "1") (pinfunction "1_1") (pintype "passive"))
      (node (ref "IC5") (pin "8") (pinfunction "VCC_8") (pintype "passive"))
      (node (ref "J2") (pin "1") (pinfunction "1_1") (pintype "passive"))
      (node (ref "P1") (pin "2") (pinfunction "2_2") (pintype "passive"))
      (node (ref "P1") (pin "9") (pinfunction "9_9") (pintype "passive"))
      (node (ref "Q5") (pin "A") (pinfunction "C_A") (pintype "passive"))
      (node (ref "R1") (pin "2") (pinfunction "2_2") (pintype "passive"))
      (node (ref "R16") (pin "2") (pinfunction "2_2") (pintype "passive"))
      (node (ref "R17") (pin "1") (pinfunction "1_1") (pintype "passive"))
      (node (ref "R2") (pin "2") (pinfunction "2_2") (pintype "passive"))
      (node (ref "R26") (pin "1") (pinfunction "1_1") (pintype "passive"))
      (node (ref "R29") (pin "2") (pinfunction "2_2") (pintype "passive"))
      (node (ref "R34") (pin "2") (pinfunction "2_2") (pintype "passive"))
      (node (ref "R37") (pin "2") (pinfunction "2_2") (pintype "passive"))
      (node (ref "R61") (pin "1") (pintype "passive"))
      (node (ref "R65") (pin "2") (pintype "passive"))
      (node (ref "R67") (pin "2") (pinfunction "2_2") (pintype "passive"))
      (node (ref "R69") (pin "1") (pinfunction "1_1") (pintype "passive"))
      (node (ref "R71") (pin "1") (pinfunction "1_1") (pintype "passive"))
      (node (ref "R9") (pin "2") (pintype "passive"))
      (node (ref "U2") (pin "4") (pinfunction "LDO33_4") (pintype "passive"))
      (node (ref "U2") (pin "5") (pinfunction "VDD5_5") (pintype "passive"))
    )
    (net (code "47") (name "NC") (class "Default")
      (node (ref "U1") (pin "3") (pinfunction "NC_3") (pintype "passive"))
    )
    (net (code "48") (name "Net-(+I-Pad1)") (class "Default")
      (node (ref "+I") (pin "1") (pintype "passive"))
      (node (ref "R7") (pin "2") (pinfunction "2_2") (pintype "passive"))
    )
    (net (code "49") (name "Net-(-I-Pad1)") (class "Default")
      (node (ref "-I") (pin "1") (pintype "passive"))
      (node (ref "R8") (pin "2") (pinfunction "2_2") (pintype "passive"))
    )
    (net (code "50") (name "Net-(BT1-+)") (class "Default")
      (node (ref "BT1") (pin "1") (pinfunction "+_1") (pintype "passive"))
      (node (ref "D2") (pin "3") (pinfunction "3_3") (pintype "passive"))
    )
    (net (code "51") (name "Net-(C16-Pad1)") (class "Default")
      (node (ref "C16") (pin "1") (pinfunction "1_1") (pintype "passive"))
      (node (ref "E2") (pin "4") (pinfunction "4_4") (pintype "passive"))
      (node (ref "JP3") (pin "1") (pinfunction "1_1") (pintype "passive"))
    )
    (net (code "52") (name "Net-(C16-Pad2)") (class "Default")
      (node (ref "C16") (pin "2") (pinfunction "2_2") (pintype "passive"))
      (node (ref "E2") (pin "3") (pinfunction "3_3") (pintype "passive"))
      (node (ref "JP3") (pin "2") (pinfunction "2_2") (pintype "passive"))
    )
    (net (code "53") (name "Net-(C19-Pad1)") (class "Default")
      (node (ref "C19") (pin "1") (pinfunction "1_1") (pintype "passive"))
      (node (ref "R24") (pin "2") (pinfunction "2_2") (pintype "passive"))
    )
    (net (code "54") (name "Net-(C19-Pad2)") (class "Default")
      (node (ref "C19") (pin "2") (pinfunction "2_2") (pintype "passive"))
      (node (ref "R12") (pin "2") (pinfunction "2_2") (pintype "passive"))
      (node (ref "RT1") (pin "1") (pinfunction "1_1") (pintype "passive"))
      (node (ref "U_N1") (pin "1") (pintype "passive"))
    )
    (net (code "55") (name "Net-(CT1-Pad1)") (class "Default")
      (node (ref "CT1") (pin "1") (pinfunction "1_1") (pintype "passive"))
      (node (ref "R4") (pin "2") (pinfunction "2_2") (pintype "passive"))
      (node (ref "R5") (pin "2") (pinfunction "2_2") (pintype "passive"))
    )
    (net (code "56") (name "Net-(CT1-Pad2)") (class "Default")
      (node (ref "CT1") (pin "2") (pinfunction "2_2") (pintype "passive"))
      (node (ref "R3") (pin "1") (pinfunction "1_1") (pintype "passive"))
      (node (ref "R6") (pin "2") (pinfunction "2_2") (pintype "passive"))
    )
    (net (code "57") (name "Net-(D1-K)") (class "Default")
      (node (ref "D1") (pin "2") (pinfunction "K_2") (pintype "passive"))
      (node (ref "IC2") (pin "2") (pinfunction "Vin_2") (pintype "passive"))
      (node (ref "TP_I_BT1") (pin "1") (pinfunction "1_1") (pintype "passive"))
    )
    (net (code "58") (name "Net-(D2-Pad1)") (class "Default")
      (node (ref "D2") (pin "1") (pinfunction "1_1") (pintype "passive"))
      (node (ref "TP_I_BT1") (pin "2") (pinfunction "2_2") (pintype "passive"))
    )
    (net (code "59") (name "Net-(D2-Pad2)") (class "Default")
      (node (ref "D2") (pin "2") (pinfunction "2_2") (pintype "passive"))
      (node (ref "TX_BT") (pin "1") (pinfunction "1_1") (pintype "passive"))
    )
    (net (code "60") (name "Net-(D5-K)") (class "Default")
      (node (ref "D5") (pin "2") (pinfunction "K_2") (pintype "passive"))
      (node (ref "D7") (pin "1") (pinfunction "A_1") (pintype "passive"))
      (node (ref "V+") (pin "1") (pintype "passive"))
    )
    (net (code "61") (name "Net-(D6-K)") (class "Default")
      (node (ref "D6") (pin "2") (pinfunction "K_2") (pintype "passive"))
      (node (ref "D8") (pin "1") (pinfunction "A_1") (pintype "passive"))
      (node (ref "V_") (pin "1") (pintype "passive"))
    )
    (net (code "62") (name "Net-(D7-K)") (class "Default")
      (node (ref "D7") (pin "2") (pinfunction "K_2") (pintype "passive"))
      (node (ref "D8") (pin "2") (pinfunction "K_2") (pintype "passive"))
      (node (ref "R63") (pin "1") (pinfunction "1_1") (pintype "passive"))
    )
    (net (code "63") (name "Net-(E2-Pad1)") (class "Default")
      (node (ref "E2") (pin "1") (pinfunction "1_1") (pintype "passive"))
      (node (ref "R72") (pin "2") (pinfunction "2_2") (pintype "passive"))
    )
    (net (code "64") (name "Net-(IC2-Vout)") (class "Default")
      (node (ref "IC2") (pin "3") (pinfunction "Vout_3") (pintype "passive"))
      (node (ref "R26") (pin "2") (pinfunction "2_2") (pintype "passive"))
    )
    (net (code "65") (name "Net-(JP2-Pad1)") (class "Default")
      (node (ref "JP2") (pin "1") (pinfunction "1_1") (pintype "passive"))
      (node (ref "R65") (pin "1") (pintype "passive"))
    )
    (net (code "66") (name "Net-(JP2-Pad2)") (class "Default")
      (node (ref "JP2") (pin "2") (pinfunction "2_2") (pintype "passive"))
      (node (ref "Q4") (pin "C") (pinfunction "C_C") (pintype "passive"))
    )
    (net (code "67") (name "Net-(LED1-1)") (class "Default")
      (node (ref "C15") (pin "1") (pinfunction "1_1") (pintype "passive"))
      (node (ref "LED1") (pin "A") (pinfunction "1_A") (pintype "passive"))
      (node (ref "R73") (pin "2") (pinfunction "2_2") (pintype "passive"))
    )
    (net (code "68") (name "Net-(LED2-1)") (class "Default")
      (node (ref "LED2") (pin "A") (pinfunction "1_A") (pintype "passive"))
      (node (ref "R29") (pin "1") (pinfunction "1_1") (pintype "passive"))
    )
    (net (code "69") (name "Net-(LED2-2)") (class "Default")
      (node (ref "LED2") (pin "K") (pinfunction "2_K") (pintype "passive"))
      (node (ref "Q3") (pin "E") (pinfunction "E_E") (pintype "passive"))
    )
    (net (code "70") (name "Net-(Q1-B)") (class "Default")
      (node (ref "Q1") (pin "1") (pinfunction "B_1") (pintype "passive"))
      (node (ref "R19") (pin "2") (pinfunction "2_2") (pintype "passive"))
      (node (ref "R22") (pin "1") (pinfunction "1_1") (pintype "passive"))
      (node (ref "R31") (pin "2") (pinfunction "2_2") (pintype "passive"))
    )
    (net (code "71") (name "Net-(Q2-PadB)") (class "Default")
      (node (ref "Q2") (pin "B") (pinfunction "B_B") (pintype "passive"))
      (node (ref "R18") (pin "2") (pinfunction "2_2") (pintype "passive"))
    )
    (net (code "72") (name "Net-(Q2-PadC)") (class "Default")
      (node (ref "Q2") (pin "C") (pinfunction "C_C") (pintype "passive"))
      (node (ref "R30") (pin "1") (pinfunction "1_1") (pintype "passive"))
      (node (ref "R32") (pin "1") (pinfunction "1_1") (pintype "passive"))
    )
    (net (code "73") (name "Net-(Q3-PadB)") (class "Default")
      (node (ref "Q3") (pin "B") (pinfunction "B_B") (pintype "passive"))
      (node (ref "R28") (pin "1") (pintype "passive"))
      (node (ref "R61") (pin "2") (pintype "passive"))
    )
    (net (code "74") (name "Net-(Q4-PadB)") (class "Default")
      (node (ref "Q4") (pin "B") (pinfunction "B_B") (pintype "passive"))
      (node (ref "R70") (pin "1") (pintype "passive"))
    )
    (net (code "75") (name "Net-(Q5-E)") (class "Default")
      (node (ref "Q5") (pin "K") (pinfunction "E_K") (pintype "passive"))
      (node (ref "R33") (pin "2") (pintype "passive"))
      (node (ref "R35") (pin "2") (pintype "passive"))
    )
    (net (code "76") (name "Net-(Q6-PadB)") (class "Default")
      (node (ref "Q6") (pin "B") (pinfunction "B_B") (pintype "passive"))
      (node (ref "R33") (pin "1") (pintype "passive"))
    )
    (net (code "77") (name "Net-(R11-Pad1)") (class "Default")
      (node (ref "R11") (pin "1") (pinfunction "1_1") (pintype "passive"))
      (node (ref "R23") (pin "2") (pinfunction "2_2") (pintype "passive"))
    )
    (net (code "78") (name "Net-(R12-Pad1)") (class "Default")
      (node (ref "R12") (pin "1") (pinfunction "1_1") (pintype "passive"))
      (node (ref "R13") (pin "2") (pinfunction "2_2") (pintype "passive"))
    )
    (net (code "79") (name "Net-(R13-Pad1)") (class "Default")
      (node (ref "R13") (pin "1") (pinfunction "1_1") (pintype "passive"))
      (node (ref "R14") (pin "2") (pinfunction "2_2") (pintype "passive"))
    )
    (net (code "80") (name "Net-(R14-Pad1)") (class "Default")
      (node (ref "R14") (pin "1") (pinfunction "1_1") (pintype "passive"))
      (node (ref "R15") (pin "2") (pinfunction "2_2") (pintype "passive"))
    )
    (net (code "81") (name "Net-(R15-Pad1)") (class "Default")
      (node (ref "R15") (pin "1") (pinfunction "1_1") (pintype "passive"))
      (node (ref "R23") (pin "1") (pinfunction "1_1") (pintype "passive"))
    )
    (net (code "82") (name "Net-(R18-Pad1)") (class "Default")
      (node (ref "R18") (pin "1") (pinfunction "1_1") (pintype "passive"))
      (node (ref "R21") (pin "2") (pinfunction "2_2") (pintype "passive"))
      (node (ref "R27") (pin "2") (pinfunction "2_2") (pintype "passive"))
    )
    (net (code "83") (name "Net-(R74-Pad1)") (class "Default")
      (node (ref "R74") (pin "1") (pinfunction "1_1") (pintype "passive"))
      (node (ref "R75") (pin "1") (pinfunction "1_1") (pintype "passive"))
    )
    (net (code "84") (name "Net-(U1-VDD)") (class "Default")
      (node (ref "C21") (pin "2") (pinfunction "2_2") (pintype "passive"))
      (node (ref "R62") (pin "2") (pinfunction "2_2") (pintype "passive"))
      (node (ref "R75") (pin "2") (pinfunction "2_2") (pintype "passive"))
      (node (ref "R76") (pin "2") (pinfunction "2_2") (pintype "passive"))
      (node (ref "U1") (pin "2") (pinfunction "VDD_2") (pintype "passive"))
    )
    (net (code "85") (name "Net-(U2-CTI)") (class "Default")
      (node (ref "G1") (pin "1") (pinfunction "1_1") (pintype "passive"))
      (node (ref "U2") (pin "48") (pinfunction "CTI_48") (pintype "passive"))
    )
    (net (code "86") (name "Net-(U2-CTO)") (class "Default")
      (node (ref "G1") (pin "2") (pinfunction "2_2") (pintype "passive"))
      (node (ref "U2") (pin "1") (pinfunction "CTO_1") (pintype "passive"))
    )
    (net (code "87") (name "Net-(Z1-K)") (class "Default")
      (node (ref "D4") (pin "1") (pintype "passive"))
      (node (ref "R24") (pin "1") (pinfunction "1_1") (pintype "passive"))
      (node (ref "Z1") (pin "2") (pinfunction "K_2") (pintype "passive"))
    )
    (net (code "88") (name "Net-(Z4-K)") (class "Default")
      (node (ref "D4") (pin "2") (pintype "passive"))
      (node (ref "R25") (pin "2") (pinfunction "2_2") (pintype "passive"))
      (node (ref "R63") (pin "2") (pinfunction "2_2") (pintype "passive"))
      (node (ref "Z4") (pin "2") (pinfunction "K_2") (pintype "passive"))
    )
    (net (code "89") (name "REF") (class "Default")
      (node (ref "C18") (pin "1") (pinfunction "1_1") (pintype "passive"))
      (node (ref "U2") (pin "7") (pinfunction "REF_7") (pintype "passive"))
    )
    (net (code "90") (name "unconnected-(LCD1-SEG1-Pad1)") (class "Default")
      (node (ref "LCD1") (pin "1") (pinfunction "SEG1_1") (pintype "passive"))
    )
    (net (code "91") (name "unconnected-(LCD1-SEG3-Pad3)") (class "Default")
      (node (ref "LCD1") (pin "3") (pinfunction "SEG3_3") (pintype "passive"))
    )
    (net (code "92") (name "unconnected-(LCD1-SEG4-Pad4)") (class "Default")
      (node (ref "LCD1") (pin "4") (pinfunction "SEG4_4") (pintype "passive"))
    )
    (net (code "93") (name "unconnected-(LCD1-SEG5-Pad5)") (class "Default")
      (node (ref "LCD1") (pin "5") (pinfunction "SEG5_5") (pintype "passive"))
    )
    (net (code "94") (name "unconnected-(LCD1-SEG6-Pad6)") (class "Default")
      (node (ref "LCD1") (pin "6") (pinfunction "SEG6_6") (pintype "passive"))
    )
    (net (code "95") (name "unconnected-(LCD1-SEG7-Pad7)") (class "Default")
      (node (ref "LCD1") (pin "7") (pinfunction "SEG7_7") (pintype "passive"))
    )
    (net (code "96") (name "unconnected-(LCD1-SEG23-Pad23)") (class "Default")
      (node (ref "LCD1") (pin "23") (pinfunction "SEG23_23") (pintype "passive"))
    )
  )
)
